# cdh.net
KiCad netlist of a schematic drawn in Altium Designer
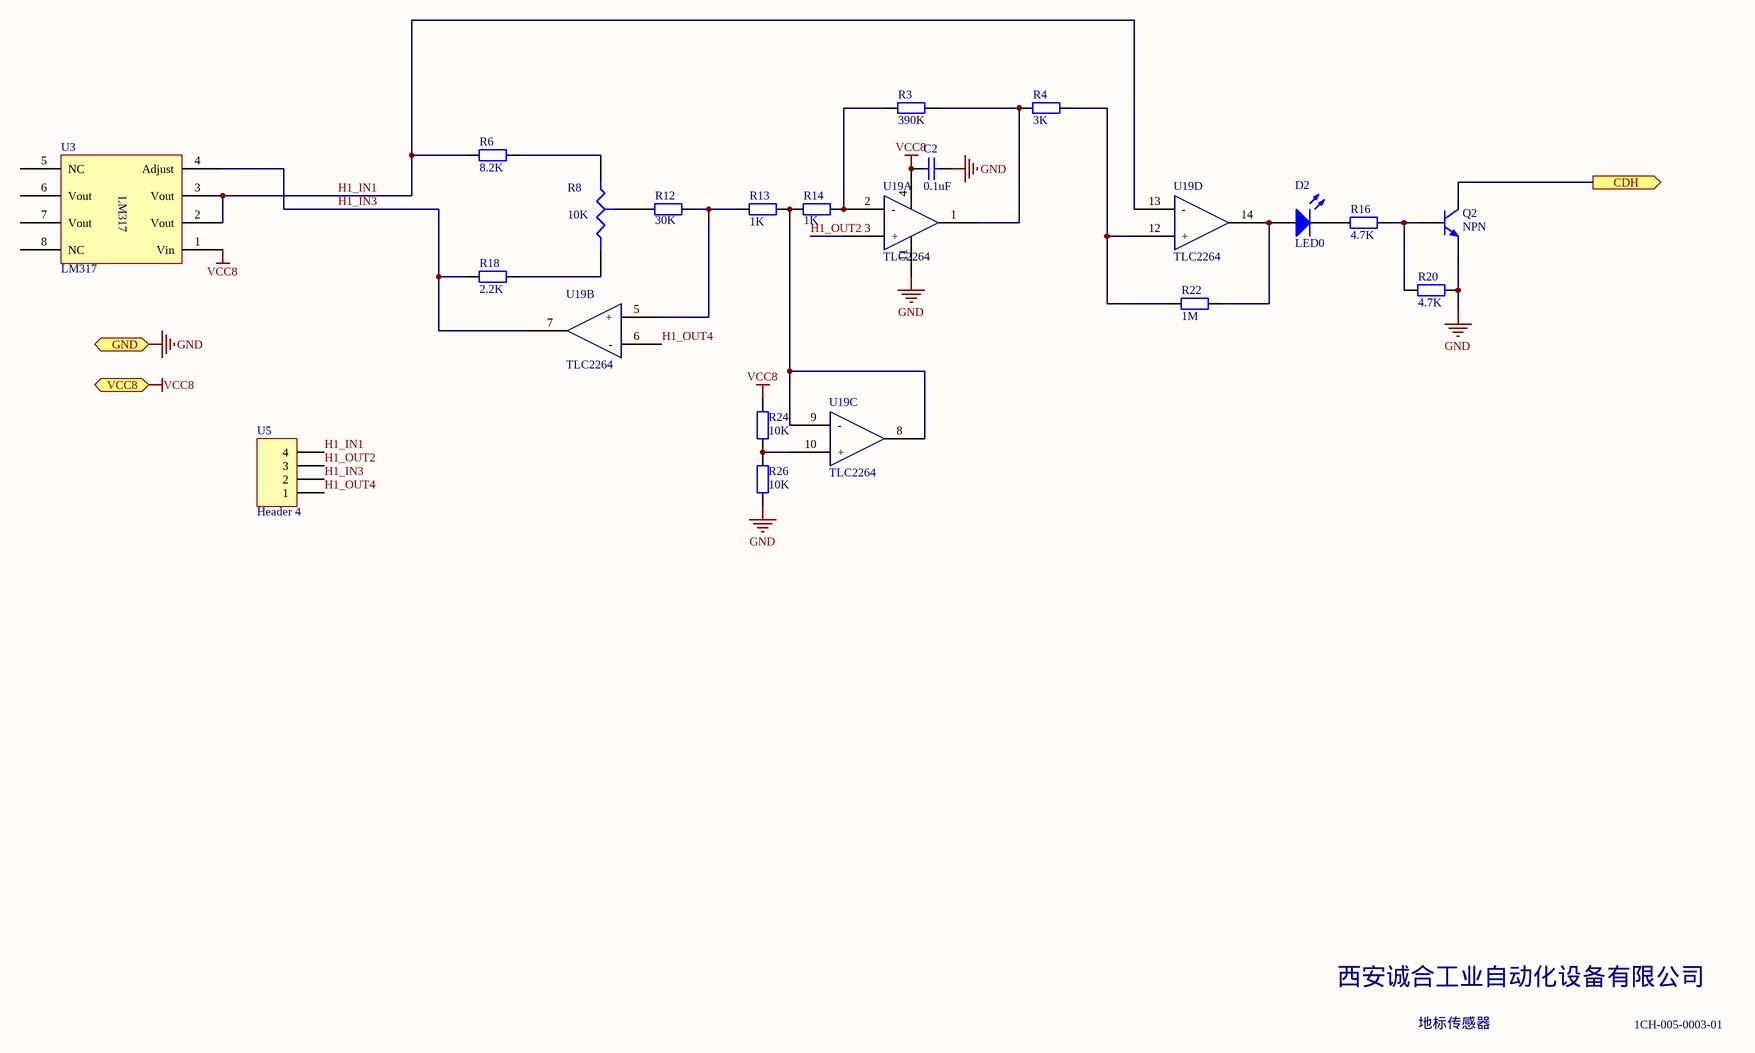
[diagram p0: cdh.SchDoc]

(export (version "E")
  (design (tool "Eeschema 10.0.6"))
  (components
    (comp (ref "C2")
      (value "0.1uF")
      (footprint "C0805")
      (description "Capacitor (Semiconductor SIM Model)")
      (fields (field (name "PUBLISHER") "Altium Limited"))
      (libsource (lib "Miscellaneous Devices") (part "Cap Semi"))
    )
    (comp (ref "D2")
      (value "LED0")
      (footprint "LED1")
      (description "Typical INFRARED GaAs LED")
      (fields (field (name "PUBLISHER") "Altium Limited"))
      (libsource (lib "Miscellaneous Devices") (part "LED0"))
    )
    (comp (ref "Q2")
      (value "NPN")
      (footprint "SOT-23")
      (description "NPN Bipolar Transistor")
      (fields (field (name "PUBLISHER") "Altium Limited"))
      (libsource (lib "Miscellaneous Devices") (part "NPN"))
    )
    (comp (ref "R3")
      (value "390K")
      (footprint "0805")
      (description "Resistor")
      (fields (field (name "PUBLISHER") "Altium Limited"))
      (libsource (lib "") (part "Res2_1"))
    )
    (comp (ref "R4")
      (value "3K")
      (footprint "0805")
      (description "Resistor")
      (fields (field (name "PUBLISHER") "Altium Limited"))
      (libsource (lib "") (part "Res2_1"))
    )
    (comp (ref "R6")
      (value "8.2K")
      (footprint "0805")
      (description "Resistor")
      (fields (field (name "PUBLISHER") "Altium Limited"))
      (libsource (lib "") (part "Res2_1"))
    )
    (comp (ref "R8")
      (value "10K")
      (footprint "3224W")
      (description "Tapped Resistor")
      (fields (field (name "Comment") "Res Tap") (field (name "PUBLISHER") "Altium Limited"))
      (libsource (lib "Miscellaneous Devices") (part "Res Tap"))
    )
    (comp (ref "R12")
      (value "30K")
      (footprint "0805")
      (description "Resistor")
      (fields (field (name "PUBLISHER") "Altium Limited"))
      (libsource (lib "") (part "Res2_1"))
    )
    (comp (ref "R13")
      (value "1K")
      (footprint "0805")
      (description "Resistor")
      (fields (field (name "PUBLISHER") "Altium Limited"))
      (libsource (lib "") (part "Res2_1"))
    )
    (comp (ref "R14")
      (value "1K")
      (footprint "0805")
      (description "Resistor")
      (fields (field (name "PUBLISHER") "Altium Limited"))
      (libsource (lib "Miscellaneous Devices") (part "Res2"))
    )
    (comp (ref "R16")
      (value "4.7K")
      (footprint "0603")
      (description "Resistor")
      (fields (field (name "PUBLISHER") "Altium Limited"))
      (libsource (lib "") (part "Res2_1"))
    )
    (comp (ref "R18")
      (value "2.2K")
      (footprint "0805")
      (description "Resistor")
      (fields (field (name "PUBLISHER") "Altium Limited"))
      (libsource (lib "") (part "Res2_1"))
    )
    (comp (ref "R20")
      (value "4.7K")
      (footprint "0603")
      (description "Resistor")
      (fields (field (name "PUBLISHER") "Altium Limited"))
      (libsource (lib "") (part "Res2_1"))
    )
    (comp (ref "R22")
      (value "1M")
      (footprint "0805")
      (description "Resistor")
      (fields (field (name "PUBLISHER") "Altium Limited"))
      (libsource (lib "") (part "Res2_1"))
    )
    (comp (ref "R24")
      (value "10K")
      (footprint "0805")
      (description "Resistor")
      (fields (field (name "PUBLISHER") "Altium Limited"))
      (libsource (lib "") (part "Res2_2"))
    )
    (comp (ref "R26")
      (value "10K")
      (footprint "0805")
      (description "Resistor")
      (fields (field (name "PUBLISHER") "Altium Limited"))
      (libsource (lib "") (part "Res2_2"))
    )
    (comp (ref "U3") (value "LM317") (footprint "SO-8") (libsource (lib "磁导航") (part "LM317")))
    (comp (ref "U5")
      (value "Header 4")
      (footprint "PIN4")
      (description "Header, 4-Pin")
      (fields (field (name "PUBLISHER") "Altium Limited"))
      (libsource (lib "Miscellaneous Connectors") (part "Header 4"))
    )
    (comp (ref "U19") (value "TLC2264") (footprint "TSSOP14") (libsource (lib "EXPLORER") (part "TLC2264")))
  )
  (nets
    (net (code "1") (name "/CDH") (class "Default")
      (node (ref "Q2") (pin "1") (pinfunction "C_1") (pintype "passive"))
    )
    (net (code "2") (name "/H1_IN1") (class "Default")
      (node (ref "R6") (pin "1") (pinfunction "1_1") (pintype "passive"))
      (node (ref "U19") (pin "13") (pinfunction "-_13") (pintype "passive"))
      (node (ref "U3") (pin "2") (pinfunction "Vout_2") (pintype "passive"))
      (node (ref "U3") (pin "3") (pinfunction "Vout_3") (pintype "passive"))
      (node (ref "U5") (pin "4") (pinfunction "4_4") (pintype "passive"))
    )
    (net (code "3") (name "/H1_IN3") (class "Default")
      (node (ref "R18") (pin "1") (pinfunction "1_1") (pintype "passive"))
      (node (ref "U19") (pin "7") (pinfunction "2OUT_7") (pintype "passive"))
      (node (ref "U3") (pin "4") (pinfunction "Adjust_4") (pintype "passive"))
      (node (ref "U5") (pin "2") (pinfunction "2_2") (pintype "passive"))
    )
    (net (code "4") (name "/H1_OUT2") (class "Default")
      (node (ref "U19") (pin "3") (pinfunction "+_3") (pintype "passive"))
      (node (ref "U5") (pin "3") (pinfunction "3_3") (pintype "passive"))
    )
    (net (code "5") (name "/H1_OUT4") (class "Default")
      (node (ref "U19") (pin "6") (pinfunction "-_6") (pintype "passive"))
      (node (ref "U5") (pin "1") (pinfunction "1_1") (pintype "passive"))
    )
    (net (code "6") (name "GND") (class "Default")
      (node (ref "C2") (pin "1") (pinfunction "1_1") (pintype "passive"))
      (node (ref "Q2") (pin "3") (pinfunction "E_3") (pintype "passive"))
      (node (ref "R20") (pin "2") (pinfunction "2_2") (pintype "passive"))
      (node (ref "R26") (pin "1") (pinfunction "1_1") (pintype "passive"))
      (node (ref "U19") (pin "11") (pinfunction "GND_11") (pintype "passive"))
    )
    (net (code "7") (name "Net-(D2-A)") (class "Default")
      (node (ref "D2") (pin "1") (pinfunction "A_1") (pintype "passive"))
      (node (ref "R22") (pin "2") (pinfunction "2_2") (pintype "passive"))
      (node (ref "U19") (pin "14") (pinfunction "4OUT_14") (pintype "passive"))
    )
    (net (code "8") (name "Net-(D2-K)") (class "Default")
      (node (ref "D2") (pin "2") (pinfunction "K_2") (pintype "passive"))
      (node (ref "R16") (pin "1") (pinfunction "1_1") (pintype "passive"))
    )
    (net (code "9") (name "Net-(Q2-B)") (class "Default")
      (node (ref "Q2") (pin "2") (pinfunction "B_2") (pintype "passive"))
      (node (ref "R16") (pin "2") (pinfunction "2_2") (pintype "passive"))
      (node (ref "R20") (pin "1") (pinfunction "1_1") (pintype "passive"))
    )
    (net (code "10") (name "Net-(R8-A)") (class "Default")
      (node (ref "R6") (pin "2") (pinfunction "2_2") (pintype "passive"))
      (node (ref "R8") (pin "1") (pinfunction "A_1") (pintype "passive"))
    )
    (net (code "11") (name "Net-(R8-B)") (class "Default")
      (node (ref "R18") (pin "2") (pinfunction "2_2") (pintype "passive"))
      (node (ref "R8") (pin "2") (pinfunction "B_2") (pintype "passive"))
    )
    (net (code "12") (name "Net-(R8-TAP)") (class "Default")
      (node (ref "R12") (pin "1") (pinfunction "1_1") (pintype "passive"))
      (node (ref "R8") (pin "3") (pinfunction "TAP_3") (pintype "passive"))
    )
    (net (code "13") (name "Net-(U19A--)") (class "Default")
      (node (ref "R14") (pin "1") (pinfunction "1_1") (pintype "passive"))
      (node (ref "R3") (pin "1") (pinfunction "1_1") (pintype "passive"))
      (node (ref "U19") (pin "2") (pinfunction "-_2") (pintype "passive"))
    )
    (net (code "14") (name "Net-(U19A-1OUT)") (class "Default")
      (node (ref "R3") (pin "2") (pinfunction "2_2") (pintype "passive"))
      (node (ref "R4") (pin "1") (pinfunction "1_1") (pintype "passive"))
      (node (ref "U19") (pin "1") (pinfunction "1OUT_1") (pintype "passive"))
    )
    (net (code "15") (name "Net-(U19B-+)") (class "Default")
      (node (ref "R12") (pin "2") (pinfunction "2_2") (pintype "passive"))
      (node (ref "R13") (pin "1") (pinfunction "1_1") (pintype "passive"))
      (node (ref "U19") (pin "5") (pinfunction "+_5") (pintype "passive"))
    )
    (net (code "16") (name "Net-(U19C-+)") (class "Default")
      (node (ref "R24") (pin "1") (pinfunction "1_1") (pintype "passive"))
      (node (ref "R26") (pin "2") (pinfunction "2_2") (pintype "passive"))
      (node (ref "U19") (pin "10") (pinfunction "+_10") (pintype "passive"))
    )
    (net (code "17") (name "Net-(U19C--)") (class "Default")
      (node (ref "R13") (pin "2") (pinfunction "2_2") (pintype "passive"))
      (node (ref "R14") (pin "2") (pinfunction "2_2") (pintype "passive"))
      (node (ref "U19") (pin "8") (pinfunction "3OUT_8") (pintype "passive"))
      (node (ref "U19") (pin "9") (pinfunction "-_9") (pintype "passive"))
    )
    (net (code "18") (name "Net-(U19D-+)") (class "Default")
      (node (ref "R22") (pin "1") (pinfunction "1_1") (pintype "passive"))
      (node (ref "R4") (pin "2") (pinfunction "2_2") (pintype "passive"))
      (node (ref "U19") (pin "12") (pinfunction "+_12") (pintype "passive"))
    )
    (net (code "19") (name "VCC8") (class "Default")
      (node (ref "C2") (pin "2") (pinfunction "2_2") (pintype "passive"))
      (node (ref "R24") (pin "2") (pinfunction "2_2") (pintype "passive"))
      (node (ref "U19") (pin "4") (pinfunction "VCC_4") (pintype "passive"))
      (node (ref "U3") (pin "1") (pinfunction "Vin_1") (pintype "passive"))
    )
    (net (code "20") (name "unconnected-(U3-NC-Pad5)") (class "Default")
      (node (ref "U3") (pin "5") (pinfunction "NC_5") (pintype "passive"))
    )
    (net (code "21") (name "unconnected-(U3-NC-Pad8)") (class "Default")
      (node (ref "U3") (pin "8") (pinfunction "NC_8") (pintype "passive"))
    )
    (net (code "22") (name "unconnected-(U3-Vout-Pad6)") (class "Default")
      (node (ref "U3") (pin "6") (pinfunction "Vout_6") (pintype "passive"))
    )
    (net (code "23") (name "unconnected-(U3-Vout-Pad7)") (class "Default")
      (node (ref "U3") (pin "7") (pinfunction "Vout_7") (pintype "passive"))
    )
  )
)
